# binary_updown.net
KiCad netlist of a schematic drawn in EAGLE
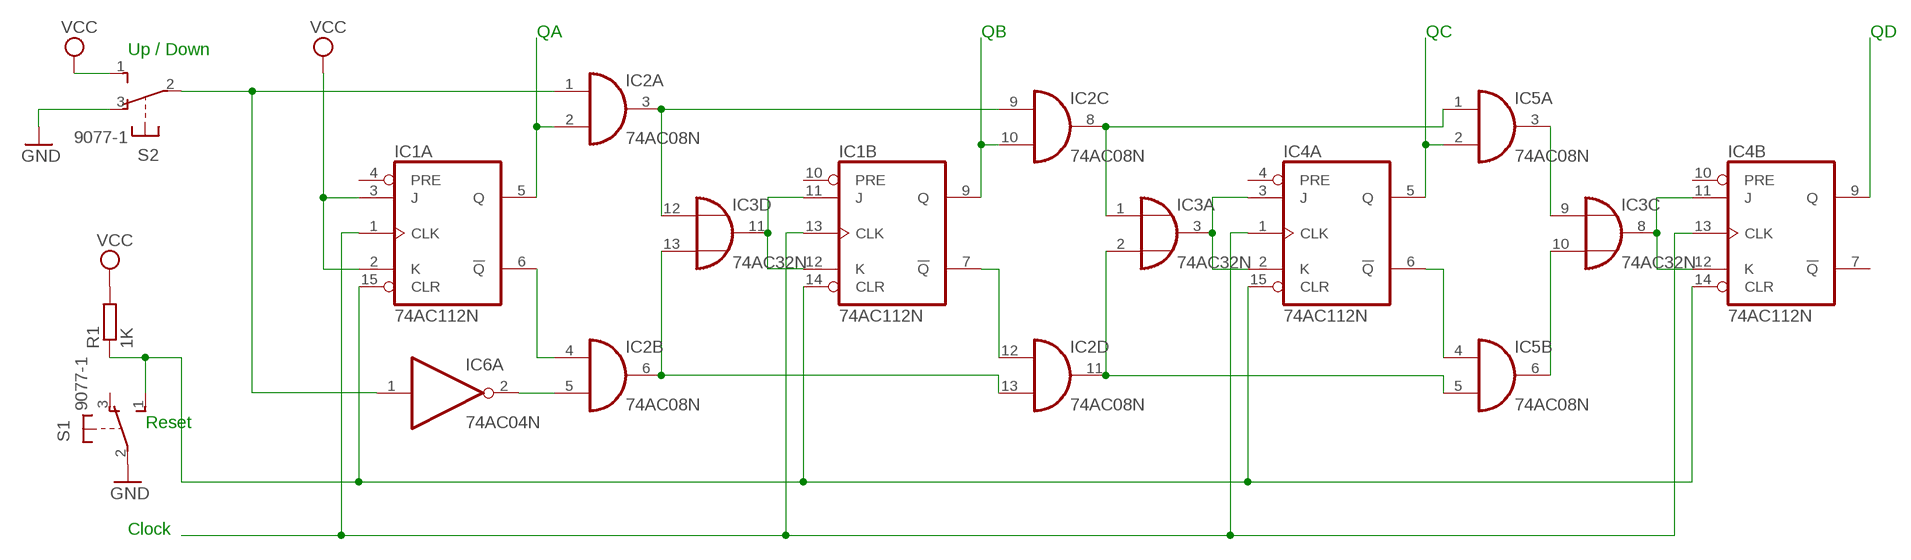
[diagram p0: schematic, sheet 1]

(export (version "E")
  (design (tool "Eeschema 10.0.6"))
  (components
    (comp (ref "IC1")
      (value "74AC112N")
      (footprint "eagle-import:DIL16")
      (libsource (lib "eagle-import") (part "74112NAC"))
    )
    (comp (ref "IC2")
      (value "74AC08N")
      (footprint "eagle-import:DIL14")
      (libsource (lib "eagle-import") (part "7408NAC"))
    )
    (comp (ref "IC3")
      (value "74AC32N")
      (footprint "eagle-import:DIL14")
      (libsource (lib "eagle-import") (part "7432NAC"))
    )
    (comp (ref "IC4")
      (value "74AC112N")
      (footprint "eagle-import:DIL16")
      (libsource (lib "eagle-import") (part "74112NAC"))
    )
    (comp (ref "IC5")
      (value "74AC08N")
      (footprint "eagle-import:DIL14")
      (libsource (lib "eagle-import") (part "7408NAC"))
    )
    (comp (ref "IC6")
      (value "74AC04N")
      (footprint "eagle-import:DIL14")
      (libsource (lib "eagle-import") (part "7404NAC"))
    )
    (comp (ref "R1")
      (value "1K")
      (footprint "eagle-import:0204_7")
      (libsource (lib "eagle-import") (part "R-EU_0204/7"))
    )
    (comp (ref "S1")
      (value "9077-1")
      (footprint "eagle-import:9077-1")
      (libsource (lib "eagle-import") (part "9077-1"))
    )
    (comp (ref "S2")
      (value "9077-1")
      (footprint "eagle-import:9077-1")
      (libsource (lib "eagle-import") (part "9077-1"))
    )
  )
  (nets
    (net (code "1") (name "GND") (class "Default")
      (node (ref "S1") (pin "2") (pinfunction "P_2") (pintype "passive"))
      (node (ref "S2") (pin "3") (pinfunction "O_3") (pintype "passive"))
    )
    (net (code "2") (name "Net-(IC1A-CLK)") (class "Default")
      (node (ref "IC1") (pin "1") (pinfunction "CLK_1") (pintype "input"))
      (node (ref "IC1") (pin "13") (pinfunction "CLK_13") (pintype "input"))
      (node (ref "IC4") (pin "1") (pinfunction "CLK_1") (pintype "input"))
      (node (ref "IC4") (pin "13") (pinfunction "CLK_13") (pintype "input"))
    )
    (net (code "3") (name "Net-(IC1A-CLR)") (class "Default")
      (node (ref "IC1") (pin "14") (pinfunction "CLR_14") (pintype "input"))
      (node (ref "IC1") (pin "15") (pinfunction "CLR_15") (pintype "input"))
      (node (ref "IC4") (pin "14") (pinfunction "CLR_14") (pintype "input"))
      (node (ref "IC4") (pin "15") (pinfunction "CLR_15") (pintype "input"))
      (node (ref "R1") (pin "1") (pinfunction "1_1") (pintype "passive"))
      (node (ref "S1") (pin "1") (pinfunction "S_1") (pintype "passive"))
    )
    (net (code "4") (name "Net-(IC1A-Q)") (class "Default")
      (node (ref "IC1") (pin "5") (pinfunction "Q_5") (pintype "output"))
      (node (ref "IC2") (pin "2") (pinfunction "I1_2") (pintype "input"))
    )
    (net (code "5") (name "Net-(IC1A-~{Q})") (class "Default")
      (node (ref "IC1") (pin "6") (pinfunction "~{Q}_6") (pintype "output"))
      (node (ref "IC2") (pin "4") (pinfunction "I0_4") (pintype "input"))
    )
    (net (code "6") (name "Net-(IC1B-J)") (class "Default")
      (node (ref "IC1") (pin "11") (pinfunction "J_11") (pintype "input"))
      (node (ref "IC1") (pin "12") (pinfunction "K_12") (pintype "input"))
      (node (ref "IC3") (pin "11") (pinfunction "O_11") (pintype "output"))
    )
    (net (code "7") (name "Net-(IC1B-Q)") (class "Default")
      (node (ref "IC1") (pin "9") (pinfunction "Q_9") (pintype "output"))
      (node (ref "IC2") (pin "10") (pinfunction "I1_10") (pintype "input"))
    )
    (net (code "8") (name "Net-(IC1B-~{Q})") (class "Default")
      (node (ref "IC1") (pin "7") (pinfunction "~{Q}_7") (pintype "output"))
      (node (ref "IC2") (pin "12") (pinfunction "I0_12") (pintype "input"))
    )
    (net (code "9") (name "Net-(IC2A-I0)") (class "Default")
      (node (ref "IC2") (pin "1") (pinfunction "I0_1") (pintype "input"))
      (node (ref "IC6") (pin "1") (pinfunction "I_1") (pintype "input"))
      (node (ref "S2") (pin "2") (pinfunction "P_2") (pintype "passive"))
    )
    (net (code "10") (name "Net-(IC2A-O)") (class "Default")
      (node (ref "IC2") (pin "3") (pinfunction "O_3") (pintype "output"))
      (node (ref "IC2") (pin "9") (pinfunction "I0_9") (pintype "input"))
      (node (ref "IC3") (pin "12") (pinfunction "I0_12") (pintype "input"))
    )
    (net (code "11") (name "Net-(IC2B-I1)") (class "Default")
      (node (ref "IC2") (pin "5") (pinfunction "I1_5") (pintype "input"))
      (node (ref "IC6") (pin "2") (pinfunction "O_2") (pintype "output"))
    )
    (net (code "12") (name "Net-(IC2B-O)") (class "Default")
      (node (ref "IC2") (pin "13") (pinfunction "I1_13") (pintype "input"))
      (node (ref "IC2") (pin "6") (pinfunction "O_6") (pintype "output"))
      (node (ref "IC3") (pin "13") (pinfunction "I1_13") (pintype "input"))
    )
    (net (code "13") (name "Net-(IC2C-O)") (class "Default")
      (node (ref "IC2") (pin "8") (pinfunction "O_8") (pintype "output"))
      (node (ref "IC3") (pin "1") (pinfunction "I0_1") (pintype "input"))
      (node (ref "IC5") (pin "1") (pinfunction "I0_1") (pintype "input"))
    )
    (net (code "14") (name "Net-(IC2D-O)") (class "Default")
      (node (ref "IC2") (pin "11") (pinfunction "O_11") (pintype "output"))
      (node (ref "IC3") (pin "2") (pinfunction "I1_2") (pintype "input"))
      (node (ref "IC5") (pin "5") (pinfunction "I1_5") (pintype "input"))
    )
    (net (code "15") (name "Net-(IC3A-O)") (class "Default")
      (node (ref "IC3") (pin "3") (pinfunction "O_3") (pintype "output"))
      (node (ref "IC4") (pin "2") (pinfunction "K_2") (pintype "input"))
      (node (ref "IC4") (pin "3") (pinfunction "J_3") (pintype "input"))
    )
    (net (code "16") (name "Net-(IC3C-I0)") (class "Default")
      (node (ref "IC3") (pin "9") (pinfunction "I0_9") (pintype "input"))
      (node (ref "IC5") (pin "3") (pinfunction "O_3") (pintype "output"))
    )
    (net (code "17") (name "Net-(IC3C-I1)") (class "Default")
      (node (ref "IC3") (pin "10") (pinfunction "I1_10") (pintype "input"))
      (node (ref "IC5") (pin "6") (pinfunction "O_6") (pintype "output"))
    )
    (net (code "18") (name "Net-(IC3C-O)") (class "Default")
      (node (ref "IC3") (pin "8") (pinfunction "O_8") (pintype "output"))
      (node (ref "IC4") (pin "11") (pinfunction "J_11") (pintype "input"))
      (node (ref "IC4") (pin "12") (pinfunction "K_12") (pintype "input"))
    )
    (net (code "19") (name "Net-(IC4A-Q)") (class "Default")
      (node (ref "IC4") (pin "5") (pinfunction "Q_5") (pintype "output"))
      (node (ref "IC5") (pin "2") (pinfunction "I1_2") (pintype "input"))
    )
    (net (code "20") (name "Net-(IC4A-~{Q})") (class "Default")
      (node (ref "IC4") (pin "6") (pinfunction "~{Q}_6") (pintype "output"))
      (node (ref "IC5") (pin "4") (pinfunction "I0_4") (pintype "input"))
    )
    (net (code "21") (name "VCC") (class "Default")
      (node (ref "IC1") (pin "2") (pinfunction "K_2") (pintype "input"))
      (node (ref "IC1") (pin "3") (pinfunction "J_3") (pintype "input"))
      (node (ref "R1") (pin "2") (pinfunction "2_2") (pintype "passive"))
      (node (ref "S2") (pin "1") (pinfunction "S_1") (pintype "passive"))
    )
    (net (code "22") (name "unconnected-(IC1A-PRE-Pad4)") (class "Default")
      (node (ref "IC1") (pin "4") (pinfunction "PRE_4") (pintype "input"))
    )
    (net (code "23") (name "unconnected-(IC1B-PRE-Pad10)") (class "Default")
      (node (ref "IC1") (pin "10") (pinfunction "PRE_10") (pintype "input"))
    )
    (net (code "24") (name "unconnected-(IC4A-PRE-Pad4)") (class "Default")
      (node (ref "IC4") (pin "4") (pinfunction "PRE_4") (pintype "input"))
    )
    (net (code "25") (name "unconnected-(IC4B-PRE-Pad10)") (class "Default")
      (node (ref "IC4") (pin "10") (pinfunction "PRE_10") (pintype "input"))
    )
    (net (code "26") (name "unconnected-(IC4B-Q-Pad9)") (class "Default")
      (node (ref "IC4") (pin "9") (pinfunction "Q_9") (pintype "output"))
    )
    (net (code "27") (name "unconnected-(IC4B-~{Q}-Pad7)") (class "Default")
      (node (ref "IC4") (pin "7") (pinfunction "~{Q}_7") (pintype "output"))
    )
    (net (code "28") (name "unconnected-(S1-O-Pad3)") (class "Default")
      (node (ref "S1") (pin "3") (pinfunction "O_3") (pintype "passive"))
    )
  )
)
